# 08_PMIC.net
KiCad netlist of a schematic drawn in Altium Designer
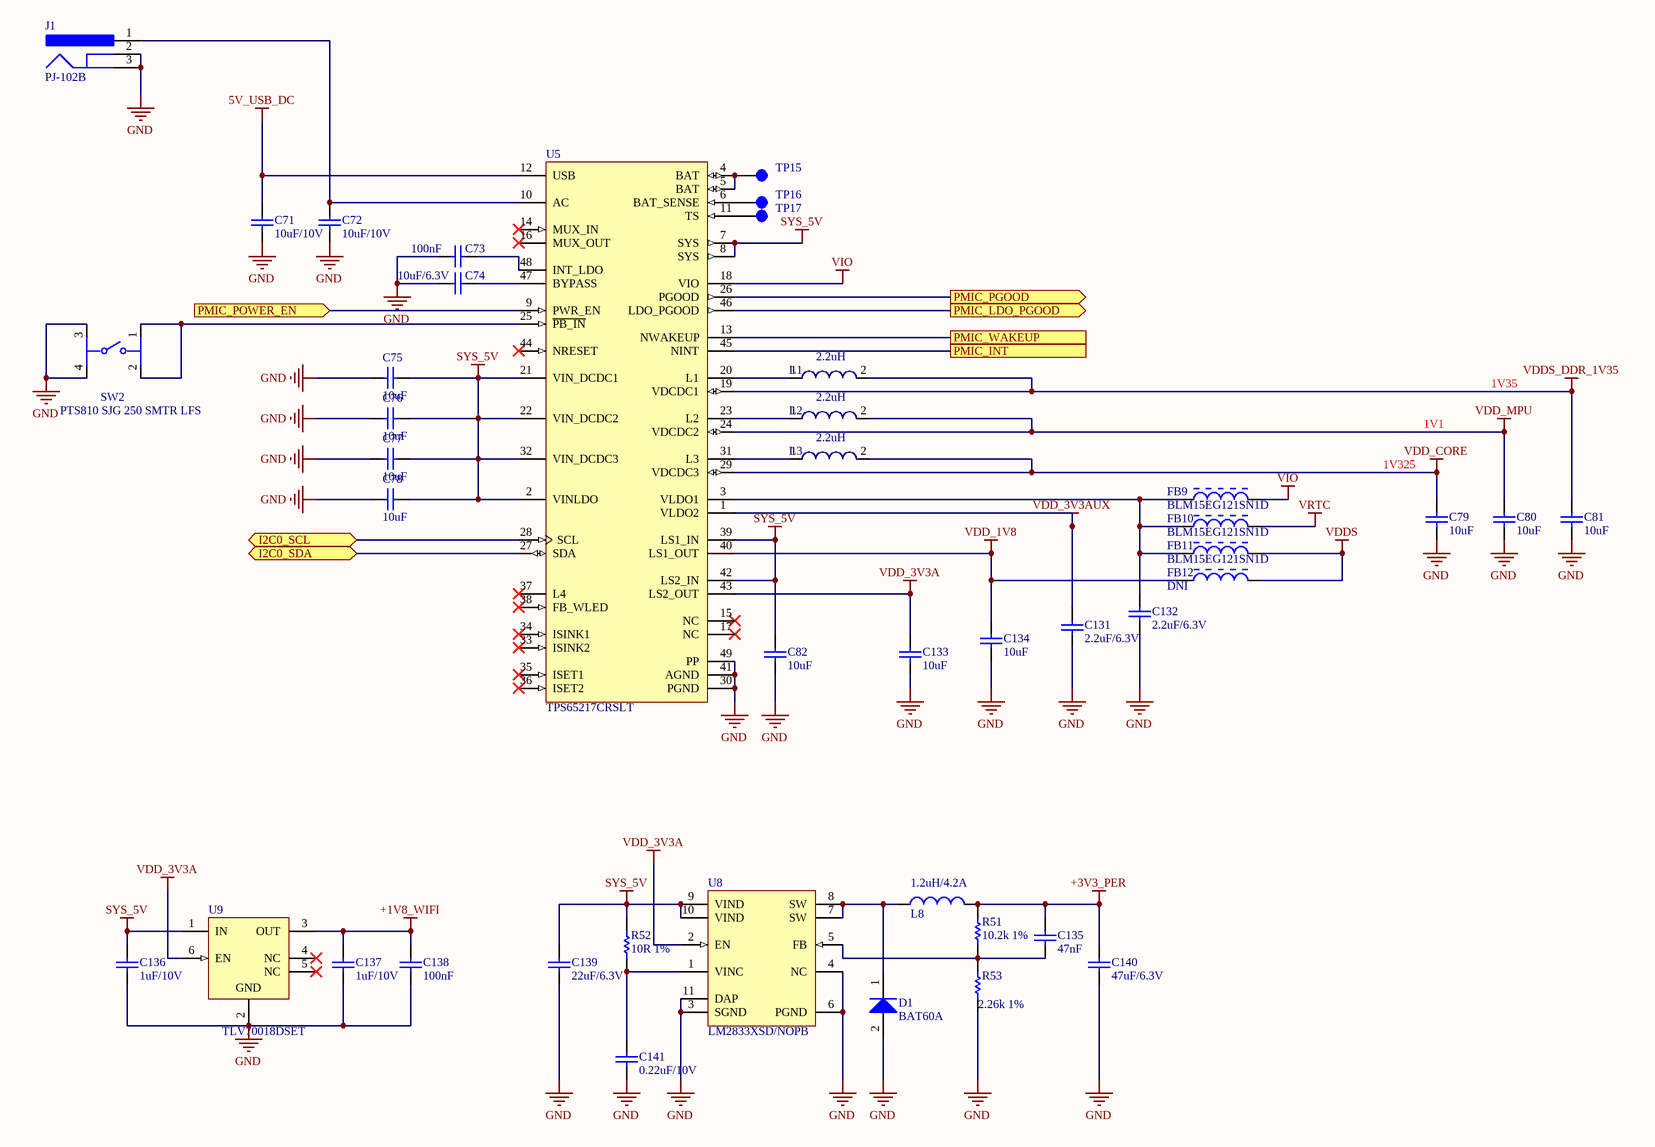
[diagram p0: 08. PMIC.SchDoc]

(export (version "E")
  (design (tool "Eeschema 10.0.6"))
  (components
    (comp (ref "C71")
      (value "10uF/10V")
      (footprint "CAPC3225X220X30LL30")
      (description "Chip Capacitor, 10 uF, +/- 10%, 25 V, -55 to 125 degC, 1210 (3225 Metric), RoHS, Tape and Reel")
      (fields (field (name "MANUFACTURER") "Murata"))
      (libsource (lib "Altium Content Vault") (part "CAP-NP-2"))
    )
    (comp (ref "C72")
      (value "10uF/10V")
      (footprint "CAPC3225X220X30LL30")
      (description "Chip Capacitor, 10 uF, +/- 10%, 25 V, -55 to 125 degC, 1210 (3225 Metric), RoHS, Tape and Reel")
      (fields (field (name "MANUFACTURER") "Murata"))
      (libsource (lib "Altium Content Vault") (part "CAP-NP-2"))
    )
    (comp (ref "C73")
      (value "100nF")
      (footprint "CAPC1005X55X25ML05T10")
      (description "Chip Capacitor, 0.1 uF, +/- 10%, 16 V, -55 to 125 degC, 0402 (1005 Metric), RoHS, Tape and Reel")
      (fields (field (name "VOLTAGE") "16V") (field (name "TOLERANCE") "10%"))
      (libsource (lib "Altium Content Vault") (part "CAP-NP-2"))
    )
    (comp (ref "C74")
      (value "10uF/6.3V")
      (footprint "CAPC1608X90X35NL10T15")
      (fields (field (name "PART NUMBER") "GRM188R60J106ME47D") (field (name "MANUFACTURER") "Murata"))
      (libsource (lib "Altium Content Vault") (part "CAP"))
    )
    (comp (ref "C75")
      (value "10uF")
      (footprint "CAPC2013X140X45NL15T25")
      (description "Chip Capacitor, 10 uF, +/- 10%, 16 V, -55 to 125 degC, 0805 (1608 Metric), RoHS, Tape and Reel")
      (fields (field (name "MANUFACTURER") "Murata") (field (name "PART NUMBER") "GRM21BR61C106KE15L"))
      (libsource (lib "AM3358_DEV_BOARD") (part "CAP"))
    )
    (comp (ref "C76")
      (value "10uF")
      (footprint "CAPC2013X140X45NL15T25")
      (description "Chip Capacitor, 10 uF, +/- 10%, 16 V, -55 to 125 degC, 0805 (1608 Metric), RoHS, Tape and Reel")
      (fields (field (name "MANUFACTURER") "Murata") (field (name "PART NUMBER") "GRM21BR61C106KE15L"))
      (libsource (lib "AM3358_DEV_BOARD") (part "CAP"))
    )
    (comp (ref "C77")
      (value "10uF")
      (footprint "CAPC2013X140X45NL15T25")
      (description "Chip Capacitor, 10 uF, +/- 10%, 16 V, -55 to 125 degC, 0805 (1608 Metric), RoHS, Tape and Reel")
      (fields (field (name "MANUFACTURER") "Murata") (field (name "PART NUMBER") "GRM21BR61C106KE15L"))
      (libsource (lib "AM3358_DEV_BOARD") (part "CAP"))
    )
    (comp (ref "C78")
      (value "10uF")
      (footprint "CAPC2013X140X45NL15T25")
      (description "Chip Capacitor, 10 uF, +/- 10%, 16 V, -55 to 125 degC, 0805 (1608 Metric), RoHS, Tape and Reel")
      (fields (field (name "MANUFACTURER") "Murata") (field (name "PART NUMBER") "GRM21BR61C106KE15L"))
      (libsource (lib "AM3358_DEV_BOARD") (part "CAP"))
    )
    (comp (ref "C79")
      (value "10uF")
      (footprint "CAPC1608X90X35ML10T15")
      (description "Chip Capacitor, 10 uF, +/- 10%, 6.3 V, -55 to 125 degC, 0603 (1608 Metric), RoHS, Tape and Reel")
      (fields (field (name "PART NUMBER") "GRM188R60J106ME47D") (field (name "MANUFACTURER") "Murata"))
      (libsource (lib "Altium Content Vault") (part "CAP"))
    )
    (comp (ref "C80")
      (value "10uF")
      (footprint "CAPC1608X90X35ML10T15")
      (description "Chip Capacitor, 10 uF, +/- 10%, 6.3 V, -55 to 125 degC, 0603 (1608 Metric), RoHS, Tape and Reel")
      (fields (field (name "PART NUMBER") "GRM188R60J106ME47D") (field (name "MANUFACTURER") "Murata"))
      (libsource (lib "Altium Content Vault") (part "CAP"))
    )
    (comp (ref "C81")
      (value "10uF")
      (footprint "CAPC1608X90X35ML10T15")
      (description "Chip Capacitor, 10 uF, +/- 10%, 6.3 V, -55 to 125 degC, 0603 (1608 Metric), RoHS, Tape and Reel")
      (fields (field (name "PART NUMBER") "GRM188R60J106ME47D") (field (name "MANUFACTURER") "Murata"))
      (libsource (lib "Altium Content Vault") (part "CAP"))
    )
    (comp (ref "C82")
      (value "10uF")
      (footprint "CAPC2013X140X45NL15T25")
      (description "Chip Capacitor, 10 uF, +/- 10%, 16 V, -55 to 125 degC, 0805 (2012 Metric), RoHS, Tape and Reel")
      (fields (field (name "MANUFACTURER") "Murata") (field (name "PART NUMBER") "GRM21BR61C106KE15L"))
      (libsource (lib "AM3358_DEV_BOARD") (part "CAP"))
    )
    (comp (ref "C131")
      (value "2.2uF/6.3V")
      (footprint "CAPC1005X60X30LL05T10")
      (fields (field (name "MANUFACTURER") "Kemet") (field (name "PART NUMBER") "C0402C225M9PAC7867"))
      (libsource (lib "Altium Content Vault") (part "CAP"))
    )
    (comp (ref "C132")
      (value "2.2uF/6.3V")
      (footprint "CAPC1005X60X30LL05T10")
      (fields (field (name "MANUFACTURER") "Kemet") (field (name "PART NUMBER") "C0402C225M9PAC7867"))
      (libsource (lib "Altium Content Vault") (part "CAP"))
    )
    (comp (ref "C133")
      (value "10uF")
      (footprint "CAPC1608X90X35ML10T15")
      (description "Chip Capacitor, 10 uF, +/- 10%, 6.3 V, -55 to 125 degC, 0603 (1608 Metric), RoHS, Tape and Reel")
      (fields (field (name "PART NUMBER") "GRM188R60J106ME47D") (field (name "MANUFACTURER") "Murata"))
      (libsource (lib "Altium Content Vault") (part "CAP"))
    )
    (comp (ref "C134")
      (value "10uF")
      (footprint "CAPC1608X90X35ML10T15")
      (description "Chip Capacitor, 10 uF, +/- 10%, 6.3 V, -55 to 125 degC, 0603 (1608 Metric), RoHS, Tape and Reel")
      (fields (field (name "PART NUMBER") "GRM188R60J106ME47D") (field (name "MANUFACTURER") "Murata"))
      (libsource (lib "Altium Content Vault") (part "CAP"))
    )
    (comp (ref "C135")
      (value "47nF")
      (footprint "CAPC1005X60X30NL05T10")
      (fields (field (name "PART NUMBER") "C0402C473J8RACTU") (field (name "MANUFACTURER") "Kemet"))
      (libsource (lib "Altium Content Vault") (part "CAP"))
    )
    (comp (ref "C136")
      (value "1uF/10V")
      (footprint "CAPC1005X55X25NL05T10")
      (fields (field (name "PART NUMBER") "GRM155R61A105KE15D") (field (name "MANUFACTURER") "Murata"))
      (libsource (lib "Altium Content Vault") (part "CAP"))
    )
    (comp (ref "C137")
      (value "1uF/10V")
      (footprint "CAPC1005X55X25NL05T10")
      (fields (field (name "PART NUMBER") "GRM155R61A105KE15D") (field (name "MANUFACTURER") "Murata"))
      (libsource (lib "Altium Content Vault") (part "CAP"))
    )
    (comp (ref "C138")
      (value "100nF")
      (footprint "CAPC1005X55X25ML05T10")
      (description "Chip Capacitor, 0.1 uF, +/- 10%, 16 V, -55 to 125 degC, 0402 (1005 Metric), RoHS, Tape and Reel")
      (fields (field (name "VOLTAGE") "16V") (field (name "TOLERANCE") "10%"))
      (libsource (lib "Altium Content Vault") (part "CAP-NP-2"))
    )
    (comp (ref "C139")
      (value "22uF/6.3V")
      (footprint "CAPC2013X140X45NL15T25")
      (fields (field (name "MANUFACTURER") "Murata") (field (name "PART NUMBER") "GRM21BR60J226ME39L"))
      (libsource (lib "Altium Content Vault") (part "CAP"))
    )
    (comp (ref "C140")
      (value "47uF/6.3V")
      (footprint "CAPC2013X145X30ML20")
      (fields (field (name "MANUFACTURER") "Murata") (field (name "PART NUMBER") "GRM21BR60G476ME15L"))
      (libsource (lib "Altium Content Vault") (part "CAP"))
    )
    (comp (ref "C141")
      (value "0.22uF/10V")
      (footprint "CAPC1005X55X25NL05T10")
      (description "Chip Capacitor, 220 nF, +/- 10%, 10 V, -55 to 85 degC, 0402 (1005 Metric), RoHS, Tape and Reel")
      (fields (field (name "MANUFACTURER") "Basic Passives") (field (name "TOLERANCE") "10%"))
      (libsource (lib "Altium Content Vault") (part "CAP-NP-2"))
    )
    (comp (ref "D1")
      (value "BAT60A")
      (footprint "INF-SOD323_V")
      (description "Silicon Schottky Diode, -55 to 85 degC, SOD323, Reel, Green")
      (fields (field (name "MANUFACTURER") "Infineon"))
      (libsource (lib "Altium Content Vault") (part "INF-D_K1A2-2"))
    )
    (comp (ref "FB9")
      (value "BLM15EG121SN1D")
      (footprint "MURA-BLM15-CHIP-2_V")
      (fields (field (name "MANUFACTURER") "Murata"))
      (libsource (lib "Altium Content Vault") (part "MURA-FB-2"))
    )
    (comp (ref "FB10")
      (value "BLM15EG121SN1D")
      (footprint "MURA-BLM15-CHIP-2_V")
      (fields (field (name "MANUFACTURER") "Murata"))
      (libsource (lib "Altium Content Vault") (part "MURA-FB-2"))
    )
    (comp (ref "FB11")
      (value "BLM15EG121SN1D")
      (footprint "MURA-BLM15-CHIP-2_V")
      (fields (field (name "MANUFACTURER") "Murata"))
      (libsource (lib "Altium Content Vault") (part "MURA-FB-2"))
    )
    (comp (ref "FB12")
      (value "DNI")
      (footprint "MURA-BLM15-CHIP-2_V")
      (fields (field (name "PARTNUMBER") "BLM15EG121SN1D") (field (name "MANUFACTURER") "Murata"))
      (libsource (lib "Altium Content Vault") (part "MURA-FB-2"))
    )
    (comp (ref "J1")
      (value "PJ-102B")
      (footprint "CUI-PJ-102B_V")
      (fields (field (name "MANUFACTURER") "CUIInc."))
      (libsource (lib "Altium Content Vault") (part "JACK-2CD3-RN"))
    )
    (comp (ref "L1")
      (value "2.2uH")
      (footprint "WE-LQS 3015")
      (description "WE-LQS SMD Power Inductor, L=2.2 µH")
      (fields (field (name "PARTNUMBER") "74404032022") (field (name "MANUFACTURER") "Wuerth Elektronik"))
      (libsource (lib "Altium Content Vault") (part "WE-IND-INDUCTOR-2"))
    )
    (comp (ref "L2")
      (value "2.2uH")
      (footprint "WE-LQS 3015")
      (description "WE-LQS SMD Power Inductor, L=2.2 µH")
      (fields (field (name "PARTNUMBER") "74404032022") (field (name "MANUFACTURER") "Wuerth Elektronik"))
      (libsource (lib "Altium Content Vault") (part "WE-IND-INDUCTOR-2"))
    )
    (comp (ref "L3")
      (value "2.2uH")
      (footprint "WE-LQS 3015")
      (description "WE-LQS SMD Power Inductor, L=2.2 µH")
      (fields (field (name "PARTNUMBER") "74404032022") (field (name "MANUFACTURER") "Wuerth Elektronik"))
      (libsource (lib "Altium Content Vault") (part "WE-IND-INDUCTOR-2"))
    )
    (comp (ref "L8")
      (value "1.2uH/4.2A")
      (footprint "LTF5022T-1R2N4R2-LC")
      (description "LTF5022T-1R2N4R2-LC")
      (libsource (lib "SyTungNguyen") (part "Inductor"))
    )
    (comp (ref "R51")
      (value "10.2k 1%")
      (footprint "RESC1005X40X25NL05T10")
      (fields (field (name "MANUFACTURER") "Yageo / Phycomp") (field (name "PART NUMBER") "RC0402FR-0710K2L"))
      (libsource (lib "Altium Content Vault") (part "RES"))
    )
    (comp (ref "R52")
      (value "10R 1%")
      (footprint "RESC1005X40X25ML05T10")
      (fields (field (name "MANUFACTURER") "Yageo / Phycomp") (field (name "PART NUMBER") "RC0402FR-0710RL"))
      (libsource (lib "Altium Content Vault") (part "RES"))
    )
    (comp (ref "R53")
      (value "2.26k 1%")
      (footprint "RESC1005X35X25NL10T10")
      (fields (field (name "MANUFACTURER") "Yageo") (field (name "PART NUMBER") "RT0402BRD072K26L"))
      (libsource (lib "Altium Content Vault") (part "RES"))
    )
    (comp (ref "SW2")
      (value "PTS810 SJG 250 SMTR LFS")
      (footprint "FP-PTS810_SJG_250_SMTR_LF-MFG")
      (description "SWITCH TACTILE SPST-NO 0.05A 16V")
      (fields
        (field (name "MANUFACTURER") "C&K Components")
        (field (name "OCTOPART") "https://octopart.com/pts810sjg250smtrlfs-c%26k+components-29380277")
      )
      (libsource (lib "Altium Content Vault") (part "1adf0dd01260c80cf25a44bfd6b99ba"))
    )
    (comp (ref "TP15") (value "Test Point") (footprint "TP") (libsource (lib "SyTungNguyen") (part "TP")))
    (comp (ref "TP16") (value "Test Point") (footprint "TP") (libsource (lib "SyTungNguyen") (part "TP")))
    (comp (ref "TP17") (value "Test Point") (footprint "TP") (libsource (lib "SyTungNguyen") (part "TP")))
    (comp (ref "U5")
      (value "TPS65217CRSLT")
      (footprint "RSL0048A")
      (libsource (lib "Altium Content Vault") (part "TI-TPS65217X-RSL48"))
    )
    (comp (ref "U8")
      (value "LM2833XSD/NOPB")
      (footprint "DSC0010A_V")
      (description "1.5MHz/3MHz 3.0A Step-Down DC-DC Switching Regulator, 10-pin LLP, Pb-Free")
      (fields (field (name "MANUFACTURER") "Texas Instruments"))
      (libsource (lib "Altium Content Vault") (part "PM-SWREG-LM2833-11"))
    )
    (comp (ref "U9")
      (value "TLV70018DSET")
      (footprint "DSE0006A_V")
      (fields (field (name "MANUFACTURER") "Texas Instruments"))
      (libsource (lib "Altium Content Vault") (part "TI-TLV7XXXXDSE6"))
    )
  )
  (nets
    (net (code "1") (name "+1V8_WIFI") (class "Default")
      (node (ref "C137") (pin "2") (pinfunction "2_2") (pintype "passive"))
      (node (ref "C138") (pin "2") (pinfunction "2_2") (pintype "passive"))
      (node (ref "U9") (pin "3") (pinfunction "OUT_3") (pintype "power_in"))
    )
    (net (code "2") (name "+3V3_PER") (class "Default")
      (node (ref "C135") (pin "2") (pinfunction "2_2") (pintype "passive"))
      (node (ref "C140") (pin "2") (pinfunction "2_2") (pintype "passive"))
      (node (ref "L8") (pin "2") (pinfunction "2_2") (pintype "passive"))
      (node (ref "R51") (pin "2") (pinfunction "2_2") (pintype "passive"))
    )
    (net (code "3") (name "/I2C0_SCL") (class "Default")
      (node (ref "U5") (pin "28") (pinfunction "SCL_28") (pintype "input"))
    )
    (net (code "4") (name "/I2C0_SDA") (class "Default")
      (node (ref "U5") (pin "27") (pinfunction "SDA_27") (pintype "bidirectional"))
    )
    (net (code "5") (name "/PMIC_INT") (class "Default")
      (node (ref "U5") (pin "45") (pinfunction "NINT_45") (pintype "tri_state"))
    )
    (net (code "6") (name "/PMIC_LDO_PGOOD") (class "Default")
      (node (ref "U5") (pin "46") (pinfunction "LDO_PGOOD_46") (pintype "output"))
    )
    (net (code "7") (name "/PMIC_PGOOD") (class "Default")
      (node (ref "U5") (pin "26") (pinfunction "PGOOD_26") (pintype "output"))
    )
    (net (code "8") (name "/PMIC_POWER_EN") (class "Default")
      (node (ref "U5") (pin "9") (pinfunction "PWR_EN_9") (pintype "input"))
    )
    (net (code "9") (name "/PMIC_WAKEUP") (class "Default")
      (node (ref "U5") (pin "13") (pinfunction "NWAKEUP_13") (pintype "tri_state"))
    )
    (net (code "10") (name "5V_USB_DC") (class "Default")
      (node (ref "C71") (pin "2") (pinfunction "2_2") (pintype "passive"))
      (node (ref "U5") (pin "12") (pinfunction "USB_12") (pintype "power_in"))
    )
    (net (code "11") (name "GND") (class "Default")
      (node (ref "C131") (pin "1") (pinfunction "1_1") (pintype "passive"))
      (node (ref "C132") (pin "1") (pinfunction "1_1") (pintype "passive"))
      (node (ref "C133") (pin "1") (pinfunction "1_1") (pintype "passive"))
      (node (ref "C134") (pin "1") (pinfunction "1_1") (pintype "passive"))
      (node (ref "C136") (pin "1") (pinfunction "1_1") (pintype "passive"))
      (node (ref "C137") (pin "1") (pinfunction "1_1") (pintype "passive"))
      (node (ref "C138") (pin "1") (pinfunction "1_1") (pintype "passive"))
      (node (ref "C139") (pin "1") (pinfunction "1_1") (pintype "passive"))
      (node (ref "C140") (pin "1") (pinfunction "1_1") (pintype "passive"))
      (node (ref "C141") (pin "1") (pinfunction "1_1") (pintype "passive"))
      (node (ref "C71") (pin "1") (pinfunction "1_1") (pintype "passive"))
      (node (ref "C72") (pin "1") (pinfunction "1_1") (pintype "passive"))
      (node (ref "C73") (pin "1") (pinfunction "1_1") (pintype "passive"))
      (node (ref "C74") (pin "1") (pinfunction "1_1") (pintype "passive"))
      (node (ref "C75") (pin "2") (pinfunction "2_2") (pintype "passive"))
      (node (ref "C76") (pin "2") (pinfunction "2_2") (pintype "passive"))
      (node (ref "C77") (pin "2") (pinfunction "2_2") (pintype "passive"))
      (node (ref "C78") (pin "2") (pinfunction "2_2") (pintype "passive"))
      (node (ref "C79") (pin "1") (pinfunction "1_1") (pintype "passive"))
      (node (ref "C80") (pin "1") (pinfunction "1_1") (pintype "passive"))
      (node (ref "C81") (pin "1") (pinfunction "1_1") (pintype "passive"))
      (node (ref "C82") (pin "1") (pinfunction "1_1") (pintype "passive"))
      (node (ref "D1") (pin "2") (pinfunction "A_2") (pintype "passive"))
      (node (ref "J1") (pin "2") (pinfunction "2_2") (pintype "passive"))
      (node (ref "J1") (pin "3") (pinfunction "3_3") (pintype "passive"))
      (node (ref "R53") (pin "1") (pinfunction "1_1") (pintype "passive"))
      (node (ref "SW2") (pin "3") (pinfunction "3_3") (pintype "passive"))
      (node (ref "SW2") (pin "4") (pinfunction "4_4") (pintype "passive"))
      (node (ref "U5") (pin "30") (pinfunction "PGND_30") (pintype "power_in"))
      (node (ref "U5") (pin "41") (pinfunction "AGND_41") (pintype "power_in"))
      (node (ref "U5") (pin "49") (pinfunction "PP_49") (pintype "power_in"))
      (node (ref "U8") (pin "11") (pinfunction "DAP_11") (pintype "power_in"))
      (node (ref "U8") (pin "3") (pinfunction "SGND_3") (pintype "power_in"))
      (node (ref "U8") (pin "4") (pinfunction "NC_4") (pintype "passive"))
      (node (ref "U8") (pin "6") (pinfunction "PGND_6") (pintype "power_in"))
      (node (ref "U9") (pin "2") (pinfunction "GND_2") (pintype "power_in"))
    )
    (net (code "12") (name "Net-(D1-K)") (class "Default")
      (node (ref "D1") (pin "1") (pinfunction "K_1") (pintype "passive"))
      (node (ref "L8") (pin "1") (pinfunction "1_1") (pintype "passive"))
      (node (ref "U8") (pin "7") (pinfunction "SW_7") (pintype "power_in"))
      (node (ref "U8") (pin "8") (pinfunction "SW_8") (pintype "power_in"))
    )
    (net (code "13") (name "Net-(TP15-Pad1)") (class "Default")
      (node (ref "TP15") (pin "1") (pintype "passive"))
      (node (ref "U5") (pin "4") (pinfunction "BAT_4") (pintype "bidirectional"))
      (node (ref "U5") (pin "5") (pinfunction "BAT_5") (pintype "bidirectional"))
    )
    (net (code "14") (name "Net-(U5-AC)") (class "Default")
      (node (ref "C72") (pin "2") (pinfunction "2_2") (pintype "passive"))
      (node (ref "J1") (pin "1") (pinfunction "1_1") (pintype "passive"))
      (node (ref "U5") (pin "10") (pinfunction "AC_10") (pintype "power_in"))
    )
    (net (code "15") (name "Net-(U5-BAT_SENSE)") (class "Default")
      (node (ref "TP16") (pin "1") (pintype "passive"))
      (node (ref "U5") (pin "6") (pinfunction "BAT_SENSE_6") (pintype "input"))
    )
    (net (code "16") (name "Net-(U5-BYPASS)") (class "Default")
      (node (ref "C74") (pin "2") (pinfunction "2_2") (pintype "passive"))
      (node (ref "U5") (pin "47") (pinfunction "BYPASS_47") (pintype "passive"))
    )
    (net (code "17") (name "Net-(U5-INT_LDO)") (class "Default")
      (node (ref "C73") (pin "2") (pinfunction "2_2") (pintype "passive"))
      (node (ref "U5") (pin "48") (pinfunction "INT_LDO_48") (pintype "passive"))
    )
    (net (code "18") (name "Net-(U5-L1)") (class "Default")
      (node (ref "L1") (pin "1") (pinfunction "1_1") (pintype "passive"))
      (node (ref "U5") (pin "20") (pinfunction "L1_20") (pintype "power_in"))
    )
    (net (code "19") (name "Net-(U5-L2)") (class "Default")
      (node (ref "L2") (pin "1") (pinfunction "1_1") (pintype "passive"))
      (node (ref "U5") (pin "23") (pinfunction "L2_23") (pintype "power_in"))
    )
    (net (code "20") (name "Net-(U5-L3)") (class "Default")
      (node (ref "L3") (pin "1") (pinfunction "1_1") (pintype "passive"))
      (node (ref "U5") (pin "31") (pinfunction "L3_31") (pintype "power_in"))
    )
    (net (code "21") (name "Net-(U5-TS)") (class "Default")
      (node (ref "TP17") (pin "1") (pintype "passive"))
      (node (ref "U5") (pin "11") (pinfunction "TS_11") (pintype "input"))
    )
    (net (code "22") (name "Net-(U5-VLDO1)") (class "Default")
      (node (ref "C132") (pin "2") (pinfunction "2_2") (pintype "passive"))
      (node (ref "FB10") (pin "1") (pinfunction "1_1") (pintype "passive"))
      (node (ref "FB11") (pin "1") (pinfunction "1_1") (pintype "passive"))
      (node (ref "FB9") (pin "1") (pinfunction "1_1") (pintype "passive"))
      (node (ref "U5") (pin "3") (pinfunction "VLDO1_3") (pintype "power_in"))
    )
    (net (code "23") (name "Net-(U5-~{PB_IN})") (class "Default")
      (node (ref "SW2") (pin "1") (pinfunction "1_1") (pintype "passive"))
      (node (ref "SW2") (pin "2") (pinfunction "2_2") (pintype "passive"))
      (node (ref "U5") (pin "25") (pinfunction "~{PB_IN}_25") (pintype "input"))
    )
    (net (code "24") (name "Net-(U8-FB)") (class "Default")
      (node (ref "C135") (pin "1") (pinfunction "1_1") (pintype "passive"))
      (node (ref "R51") (pin "1") (pinfunction "1_1") (pintype "passive"))
      (node (ref "R53") (pin "2") (pinfunction "2_2") (pintype "passive"))
      (node (ref "U8") (pin "5") (pinfunction "FB_5") (pintype "input"))
    )
    (net (code "25") (name "Net-(U8-VINC)") (class "Default")
      (node (ref "C141") (pin "2") (pinfunction "2_2") (pintype "passive"))
      (node (ref "R52") (pin "1") (pinfunction "1_1") (pintype "passive"))
      (node (ref "U8") (pin "1") (pinfunction "VINC_1") (pintype "power_in"))
    )
    (net (code "26") (name "SYS_5V") (class "Default")
      (node (ref "C136") (pin "2") (pinfunction "2_2") (pintype "passive"))
      (node (ref "C139") (pin "2") (pinfunction "2_2") (pintype "passive"))
      (node (ref "C75") (pin "1") (pinfunction "1_1") (pintype "passive"))
      (node (ref "C76") (pin "1") (pinfunction "1_1") (pintype "passive"))
      (node (ref "C77") (pin "1") (pinfunction "1_1") (pintype "passive"))
      (node (ref "C78") (pin "1") (pinfunction "1_1") (pintype "passive"))
      (node (ref "C82") (pin "2") (pinfunction "2_2") (pintype "passive"))
      (node (ref "R52") (pin "2") (pinfunction "2_2") (pintype "passive"))
      (node (ref "U5") (pin "2") (pinfunction "VINLDO_2") (pintype "power_in"))
      (node (ref "U5") (pin "21") (pinfunction "VIN_DCDC1_21") (pintype "power_in"))
      (node (ref "U5") (pin "22") (pinfunction "VIN_DCDC2_22") (pintype "power_in"))
      (node (ref "U5") (pin "32") (pinfunction "VIN_DCDC3_32") (pintype "power_in"))
      (node (ref "U5") (pin "39") (pinfunction "LS1_IN_39") (pintype "power_in"))
      (node (ref "U5") (pin "42") (pinfunction "LS2_IN_42") (pintype "power_in"))
      (node (ref "U5") (pin "7") (pinfunction "SYS_7") (pintype "output"))
      (node (ref "U5") (pin "8") (pinfunction "SYS_8") (pintype "output"))
      (node (ref "U8") (pin "10") (pinfunction "VIND_10") (pintype "power_in"))
      (node (ref "U8") (pin "9") (pinfunction "VIND_9") (pintype "power_in"))
      (node (ref "U9") (pin "1") (pinfunction "IN_1") (pintype "power_in"))
    )
    (net (code "27") (name "VDDS") (class "Default")
      (node (ref "FB11") (pin "2") (pinfunction "2_2") (pintype "passive"))
      (node (ref "FB12") (pin "2") (pinfunction "2_2") (pintype "passive"))
    )
    (net (code "28") (name "VDDS_DDR_1V35") (class "Default")
      (node (ref "C81") (pin "2") (pinfunction "2_2") (pintype "passive"))
      (node (ref "L1") (pin "2") (pinfunction "2_2") (pintype "passive"))
      (node (ref "U5") (pin "19") (pinfunction "VDCDC1_19") (pintype "bidirectional"))
    )
    (net (code "29") (name "VDD_1V8") (class "Default")
      (node (ref "C134") (pin "2") (pinfunction "2_2") (pintype "passive"))
      (node (ref "FB12") (pin "1") (pinfunction "1_1") (pintype "passive"))
      (node (ref "U5") (pin "40") (pinfunction "LS1_OUT_40") (pintype "power_in"))
    )
    (net (code "30") (name "VDD_3V3A") (class "Default")
      (node (ref "C133") (pin "2") (pinfunction "2_2") (pintype "passive"))
      (node (ref "U5") (pin "43") (pinfunction "LS2_OUT_43") (pintype "power_in"))
      (node (ref "U8") (pin "2") (pinfunction "EN_2") (pintype "input"))
      (node (ref "U9") (pin "6") (pinfunction "EN_6") (pintype "input"))
    )
    (net (code "31") (name "VDD_3V3AUX") (class "Default")
      (node (ref "C131") (pin "2") (pinfunction "2_2") (pintype "passive"))
      (node (ref "U5") (pin "1") (pinfunction "VLDO2_1") (pintype "power_in"))
    )
    (net (code "32") (name "VDD_CORE") (class "Default")
      (node (ref "C79") (pin "2") (pinfunction "2_2") (pintype "passive"))
      (node (ref "L3") (pin "2") (pinfunction "2_2") (pintype "passive"))
      (node (ref "U5") (pin "29") (pinfunction "VDCDC3_29") (pintype "bidirectional"))
    )
    (net (code "33") (name "VDD_MPU") (class "Default")
      (node (ref "C80") (pin "2") (pinfunction "2_2") (pintype "passive"))
      (node (ref "L2") (pin "2") (pinfunction "2_2") (pintype "passive"))
      (node (ref "U5") (pin "24") (pinfunction "VDCDC2_24") (pintype "bidirectional"))
    )
    (net (code "34") (name "VIO") (class "Default")
      (node (ref "FB9") (pin "2") (pinfunction "2_2") (pintype "passive"))
      (node (ref "U5") (pin "18") (pinfunction "VIO_18") (pintype "power_in"))
    )
    (net (code "35") (name "VRTC") (class "Default")
      (node (ref "FB10") (pin "2") (pinfunction "2_2") (pintype "passive"))
    )
    (net (code "36") (name "unconnected-(U5-FB_WLED-Pad38)") (class "Default")
      (node (ref "U5") (pin "38") (pinfunction "FB_WLED_38") (pintype "input+no_connect"))
    )
    (net (code "37") (name "unconnected-(U5-ISET1-Pad35)") (class "Default")
      (node (ref "U5") (pin "35") (pinfunction "ISET1_35") (pintype "input+no_connect"))
    )
    (net (code "38") (name "unconnected-(U5-ISET2-Pad36)") (class "Default")
      (node (ref "U5") (pin "36") (pinfunction "ISET2_36") (pintype "input+no_connect"))
    )
    (net (code "39") (name "unconnected-(U5-ISINK1-Pad34)") (class "Default")
      (node (ref "U5") (pin "34") (pinfunction "ISINK1_34") (pintype "input+no_connect"))
    )
    (net (code "40") (name "unconnected-(U5-ISINK2-Pad33)") (class "Default")
      (node (ref "U5") (pin "33") (pinfunction "ISINK2_33") (pintype "input+no_connect"))
    )
    (net (code "41") (name "unconnected-(U5-L4-Pad37)") (class "Default")
      (node (ref "U5") (pin "37") (pinfunction "L4_37") (pintype "power_in+no_connect"))
    )
    (net (code "42") (name "unconnected-(U5-MUX_IN-Pad14)") (class "Default")
      (node (ref "U5") (pin "14") (pinfunction "MUX_IN_14") (pintype "input+no_connect"))
    )
    (net (code "43") (name "unconnected-(U5-MUX_OUT-Pad16)") (class "Default")
      (node (ref "U5") (pin "16") (pinfunction "MUX_OUT_16") (pintype "tri_state+no_connect"))
    )
    (net (code "44") (name "unconnected-(U5-NC-Pad15)") (class "Default")
      (node (ref "U5") (pin "15") (pinfunction "NC_15") (pintype "passive+no_connect"))
    )
    (net (code "45") (name "unconnected-(U5-NC-Pad17)") (class "Default")
      (node (ref "U5") (pin "17") (pinfunction "NC_17") (pintype "passive+no_connect"))
    )
    (net (code "46") (name "unconnected-(U5-NRESET-Pad44)") (class "Default")
      (node (ref "U5") (pin "44") (pinfunction "NRESET_44") (pintype "input+no_connect"))
    )
    (net (code "47") (name "unconnected-(U9-NC-Pad4)") (class "Default")
      (node (ref "U9") (pin "4") (pinfunction "NC_4") (pintype "passive+no_connect"))
    )
    (net (code "48") (name "unconnected-(U9-NC-Pad5)") (class "Default")
      (node (ref "U9") (pin "5") (pinfunction "NC_5") (pintype "passive+no_connect"))
    )
  )
)
